# 3_Sensors.net
KiCad netlist of a schematic drawn in Altium Designer
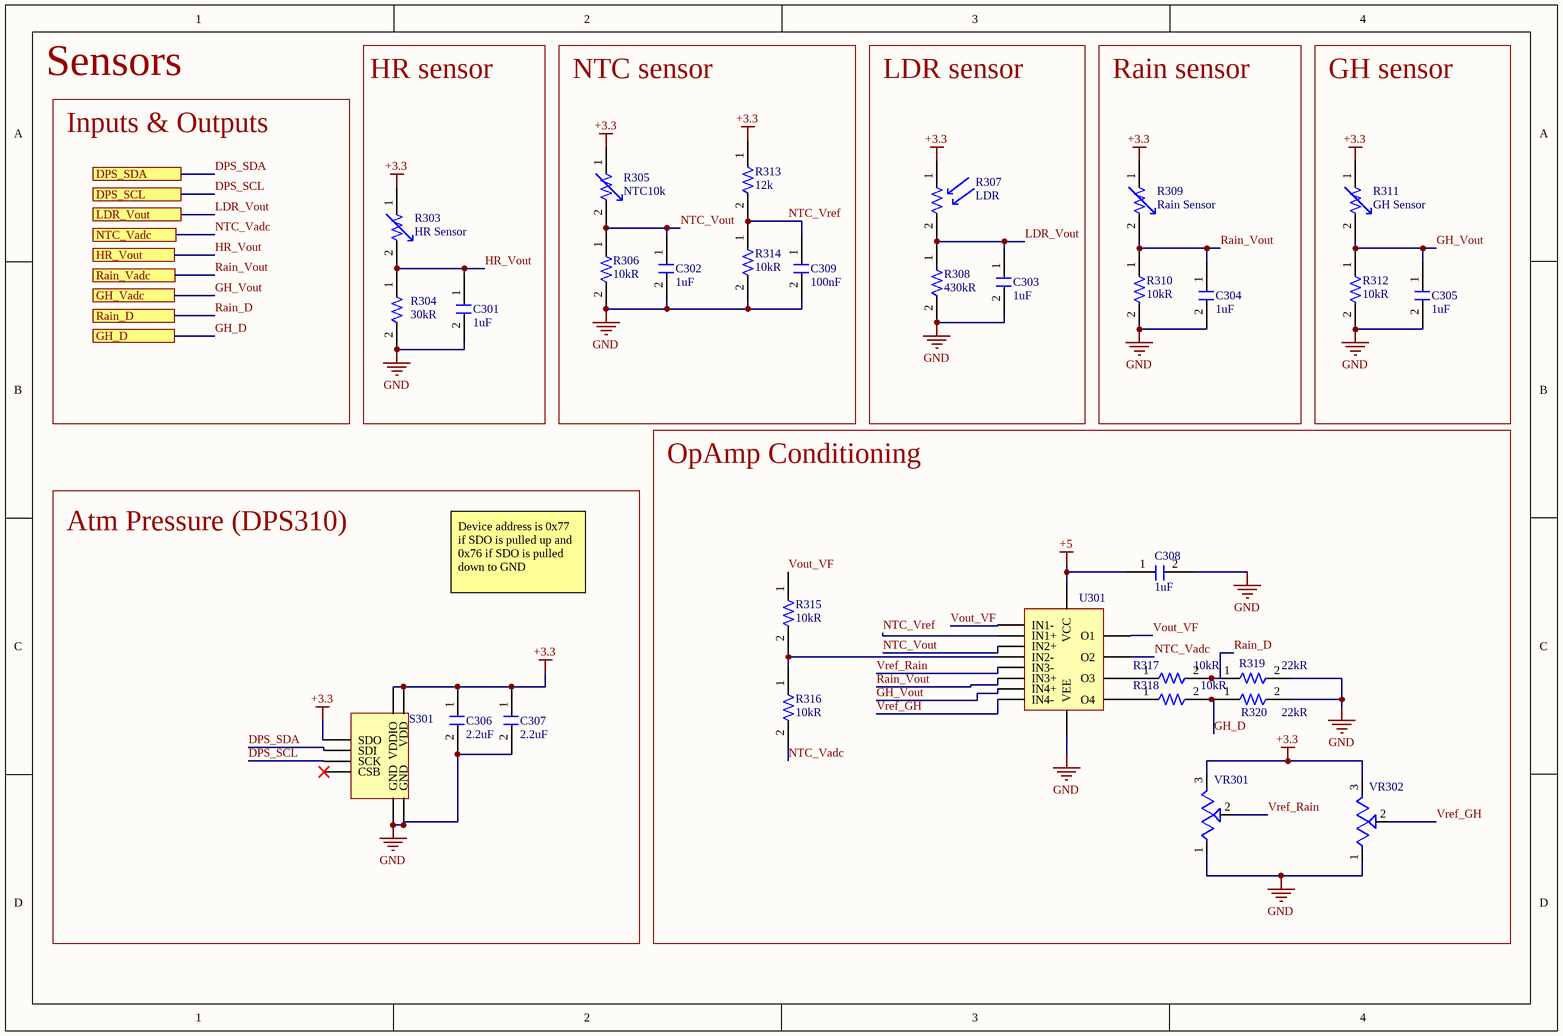
[diagram p0: [3]Sensors.SchDoc]

(export (version "E")
  (design (tool "Eeschema 10.0.6"))
  (components
    (comp (ref "C301")
      (value "885012208036")
      (footprint "C1206FNPC-RW")
      (description "Cap Cer 1UF 16V X7R 1206")
      (fields
        (field (name "MANUFACTURER") "Wurth Electronics")
        (field (name "TOLERANCE") "10%")
        (field (name "CAPACITANCE") "1uF")
        (field (name ".CREATOR") "GP")
      )
      (libsource (lib "Passives") (part "C1u-16V-1206FNPC-X7R"))
    )
    (comp (ref "C302")
      (value "885012208036")
      (footprint "C1206FNPC-RW")
      (description "Cap Cer 1UF 16V X7R 1206")
      (fields
        (field (name "MANUFACTURER") "Wurth Electronics")
        (field (name "TOLERANCE") "10%")
        (field (name "CAPACITANCE") "1uF")
        (field (name ".CREATOR") "GP")
      )
      (libsource (lib "Passives") (part "C1u-16V-1206FNPC-X7R"))
    )
    (comp (ref "C303")
      (value "885012208036")
      (footprint "C1206FNPC-RW")
      (description "Cap Cer 1UF 16V X7R 1206")
      (fields
        (field (name "MANUFACTURER") "Wurth Electronics")
        (field (name "TOLERANCE") "10%")
        (field (name "CAPACITANCE") "1uF")
        (field (name ".CREATOR") "GP")
      )
      (libsource (lib "Passives") (part "C1u-16V-1206FNPC-X7R"))
    )
    (comp (ref "C304")
      (value "885012208036")
      (footprint "C1206FNPC-RW")
      (description "Cap Cer 1UF 16V X7R 1206")
      (fields
        (field (name "MANUFACTURER") "Wurth Electronics")
        (field (name "TOLERANCE") "10%")
        (field (name "CAPACITANCE") "1uF")
        (field (name ".CREATOR") "GP")
      )
      (libsource (lib "Passives") (part "C1u-16V-1206FNPC-X7R"))
    )
    (comp (ref "C305")
      (value "885012208036")
      (footprint "C1206FNPC-RW")
      (description "Cap Cer 1UF 16V X7R 1206")
      (fields
        (field (name "MANUFACTURER") "Wurth Electronics")
        (field (name "TOLERANCE") "10%")
        (field (name "CAPACITANCE") "1uF")
        (field (name ".CREATOR") "GP")
      )
      (libsource (lib "Passives") (part "C1u-16V-1206FNPC-X7R"))
    )
    (comp (ref "C306")
      (value "2.2uF")
      (footprint "C0805FNPC-W")
      (libsource (lib "Passives") (part "C2.2u-16V-0805FTK"))
    )
    (comp (ref "C307")
      (value "2.2uF")
      (footprint "C0805FNPC-W")
      (libsource (lib "Passives") (part "C2.2u-16V-0805FTK"))
    )
    (comp (ref "C308")
      (value "885012208036")
      (footprint "C1206FNPC-RW")
      (description "Cap Cer 1UF 16V X7R 1206")
      (fields
        (field (name "MANUFACTURER") "Wurth Electronics")
        (field (name "TOLERANCE") "10%")
        (field (name "CAPACITANCE") "1uF")
        (field (name ".CREATOR") "GP")
      )
      (libsource (lib "Passives") (part "C1u-16V-1206FNPC-X7R"))
    )
    (comp (ref "C309")
      (value "885012208009")
      (footprint "C1206FNPC-RW")
      (description "Cap, 0.1ΜF, 10V, 10%, X7R, 1206")
      (fields
        (field (name "TOLERANCE") "10%")
        (field (name "CAPACITANCE") "100nF")
        (field (name ".CREATOR") "GP")
      )
      (libsource (lib "Passives") (part "C100n-10V-1206FNPC-X7R"))
    )
    (comp (ref "R303")
      (value "HR Sensor")
      (footprint "HR_Sensor")
      (description "Resistive HR Sensor. R30k at 60%@25ºC")
      (libsource (lib "CommonFiles_Library") (part "Resistive_HR_Sensor"))
    )
    (comp (ref "R304")
      (value "CRCW120630K0FKEA")
      (footprint "R1206FTK-W")
      (description "Res Thick Film 1206 30K Ohm 1% 1/4W ±100ppm/°C Molded SMD SMD Paper T/R")
      (fields
        (field (name "MANUFACTURER") "Vishay")
        (field (name "TOLERANCE") "1%")
        (field (name "RESISTANCE") "30kR")
        (field (name ".CREATOR") "GP")
      )
      (libsource (lib "Passives") (part "R30k-1206FTK"))
    )
    (comp (ref "R305")
      (value "NTC10k")
      (footprint "NTC10k_0805")
      (libsource (lib "CommonFiles_Library") (part "NTC_10k_0805"))
    )
    (comp (ref "R306")
      (value "CR0805-JW-103ELF")
      (footprint "R0805FTK")
      (fields
        (field (name "TOLERANCE") "5%")
        (field (name "RESISTANCE") "10kR")
        (field (name ".CREATOR") "DR")
      )
      (libsource (lib "Passives") (part "R10k-0805FTK"))
    )
    (comp (ref "R307")
      (value "LDR")
      (footprint "HR_Sensor")
      (libsource (lib "CommonFiles_Library") (part "LDR_LightSensor"))
    )
    (comp (ref "R308")
      (value "430kR")
      (footprint "R0805FTK")
      (libsource (lib "Passives") (part "R430k-0805FTK"))
    )
    (comp (ref "R309")
      (value "Rain Sensor")
      (footprint "EXTERNAL_SENSOR")
      (libsource (lib "CommonFiles_Library") (part "RainSensor_Resisitve"))
    )
    (comp (ref "R310")
      (value "CR0805-JW-103ELF")
      (footprint "R0805FTK")
      (fields
        (field (name "TOLERANCE") "5%")
        (field (name "RESISTANCE") "10kR")
        (field (name ".CREATOR") "DR")
      )
      (libsource (lib "Passives") (part "R10k-0805FTK"))
    )
    (comp (ref "R311")
      (value "GH Sensor")
      (footprint "EXTERNAL_SENSOR")
      (libsource (lib "CommonFiles_Library") (part "GH_Resistive_Sensor"))
    )
    (comp (ref "R312")
      (value "CR0805-JW-103ELF")
      (footprint "R0805FTK")
      (fields
        (field (name "TOLERANCE") "5%")
        (field (name "RESISTANCE") "10kR")
        (field (name ".CREATOR") "DR")
      )
      (libsource (lib "Passives") (part "R10k-0805FTK"))
    )
    (comp (ref "R313")
      (value "12k")
      (footprint "R1206")
      (libsource (lib "CommonFiles_Library") (part "R12k-1206"))
    )
    (comp (ref "R314")
      (value "CR0805-JW-103ELF")
      (footprint "R0805FTK")
      (fields
        (field (name "TOLERANCE") "5%")
        (field (name "RESISTANCE") "10kR")
        (field (name ".CREATOR") "DR")
      )
      (libsource (lib "Passives") (part "R10k-0805FTK"))
    )
    (comp (ref "R315")
      (value "CR0805-JW-103ELF")
      (footprint "R0805FTK")
      (fields
        (field (name "TOLERANCE") "5%")
        (field (name "RESISTANCE") "10kR")
        (field (name ".CREATOR") "DR")
      )
      (libsource (lib "Passives") (part "R10k-0805FTK"))
    )
    (comp (ref "R316")
      (value "CR0805-JW-103ELF")
      (footprint "R0805FTK")
      (fields
        (field (name "TOLERANCE") "5%")
        (field (name "RESISTANCE") "10kR")
        (field (name ".CREATOR") "DR")
      )
      (libsource (lib "Passives") (part "R10k-0805FTK"))
    )
    (comp (ref "R317")
      (value "CR0805-JW-103ELF")
      (footprint "R0805FTK")
      (fields
        (field (name "TOLERANCE") "5%")
        (field (name "RESISTANCE") "10kR")
        (field (name ".CREATOR") "DR")
      )
      (libsource (lib "Passives") (part "R10k-0805FTK"))
    )
    (comp (ref "R318")
      (value "CR0805-JW-103ELF")
      (footprint "R0805FTK")
      (fields
        (field (name "TOLERANCE") "5%")
        (field (name "RESISTANCE") "10kR")
        (field (name ".CREATOR") "DR")
      )
      (libsource (lib "Passives") (part "R10k-0805FTK"))
    )
    (comp (ref "R319")
      (value "22kR")
      (footprint "R0805FTK")
      (libsource (lib "Passives") (part "R22k-0805FTK"))
    )
    (comp (ref "R320")
      (value "22kR")
      (footprint "R0805FTK")
      (libsource (lib "Passives") (part "R22k-0805FTK"))
    )
    (comp (ref "S301")
      (value "DPS310XTSA1")
      (footprint "XDCR_DPS310XTSA1")
      (description "DPS310 Digital Pressure Sensor")
      (libsource (lib "CommonFiles_Library") (part "AtmPressureSensor_DPS310XTSA1"))
    )
    (comp (ref "U301")
      (value "OpAmp")
      (footprint "LM324_OpAmp")
      (libsource (lib "CommonFiles_Library") (part "LM324_OpAmp"))
    )
    (comp (ref "VR301")
      (value "Trimmer_10k_THT")
      (footprint "TRIM_3362P-1-103LF")
      (description "Trimmer, Cermet, Rest 10 Kilohms, PCB, 1 Turns, Pwr-Rtg 0.5 W, Tol 10% ¦ Bourns 3362P-1-103LF")
      (fields (field (name "MF") "Bourns") (field (name "MP") "3362P-1-103LF"))
      (libsource (lib "CommonFiles_Library") (part "Trimmer_10k_THT"))
    )
    (comp (ref "VR302")
      (value "Trimmer_10k_THT")
      (footprint "TRIM_3362P-1-103LF")
      (description "Trimmer, Cermet, Rest 10 Kilohms, PCB, 1 Turns, Pwr-Rtg 0.5 W, Tol 10% ¦ Bourns 3362P-1-103LF")
      (fields (field (name "MF") "Bourns") (field (name "MP") "3362P-1-103LF"))
      (libsource (lib "CommonFiles_Library") (part "Trimmer_10k_THT"))
    )
  )
  (nets
    (net (code "1") (name "+3.3") (class "Default")
      (node (ref "C306") (pin "1") (pinfunction "1_1") (pintype "passive"))
      (node (ref "C307") (pin "1") (pinfunction "1_1") (pintype "passive"))
      (node (ref "R303") (pin "1") (pinfunction "2_1") (pintype "passive"))
      (node (ref "R305") (pin "1") (pinfunction "2_1") (pintype "passive"))
      (node (ref "R307") (pin "1") (pinfunction "2_1") (pintype "passive"))
      (node (ref "R309") (pin "1") (pinfunction "2_1") (pintype "passive"))
      (node (ref "R311") (pin "1") (pinfunction "2_1") (pintype "passive"))
      (node (ref "R313") (pin "1") (pinfunction "2_1") (pintype "passive"))
      (node (ref "S301") (pin "5") (pinfunction "SDO_5") (pintype "passive"))
      (node (ref "S301") (pin "6") (pinfunction "VDDIO_6") (pintype "passive"))
      (node (ref "S301") (pin "8") (pinfunction "VDD_8") (pintype "passive"))
      (node (ref "VR301") (pin "3") (pinfunction "CW_3") (pintype "passive"))
      (node (ref "VR302") (pin "3") (pinfunction "CW_3") (pintype "passive"))
    )
    (net (code "2") (name "+5") (class "Default")
      (node (ref "C308") (pin "1") (pinfunction "1_1") (pintype "passive"))
      (node (ref "U301") (pin "4") (pinfunction "VCC_4") (pintype "passive"))
    )
    (net (code "3") (name "/DPS_SCL") (class "Default")
      (node (ref "S301") (pin "4") (pinfunction "SCK_4") (pintype "passive"))
    )
    (net (code "4") (name "/DPS_SDA") (class "Default")
      (node (ref "S301") (pin "3") (pinfunction "SDI_3") (pintype "passive"))
    )
    (net (code "5") (name "/GH_D") (class "Default")
      (node (ref "R318") (pin "2") (pinfunction "2_2") (pintype "passive"))
      (node (ref "R320") (pin "1") (pinfunction "1_1") (pintype "passive"))
    )
    (net (code "6") (name "/GH_Vout") (class "Default")
      (node (ref "C305") (pin "1") (pinfunction "1_1") (pintype "passive"))
      (node (ref "R311") (pin "2") (pinfunction "2_2") (pintype "passive"))
      (node (ref "R312") (pin "1") (pinfunction "1_1") (pintype "passive"))
      (node (ref "U301") (pin "12") (pinfunction "IN4+_12") (pintype "passive"))
    )
    (net (code "7") (name "/HR_Vout") (class "Default")
      (node (ref "C301") (pin "1") (pinfunction "1_1") (pintype "passive"))
      (node (ref "R303") (pin "2") (pinfunction "2_2") (pintype "passive"))
      (node (ref "R304") (pin "1") (pinfunction "1_1") (pintype "passive"))
    )
    (net (code "8") (name "/LDR_Vout") (class "Default")
      (node (ref "C303") (pin "1") (pinfunction "1_1") (pintype "passive"))
      (node (ref "R307") (pin "2") (pinfunction "2_2") (pintype "passive"))
      (node (ref "R308") (pin "1") (pinfunction "1_1") (pintype "passive"))
    )
    (net (code "9") (name "/NTC_Vadc") (class "Default")
      (node (ref "R316") (pin "2") (pinfunction "2_2") (pintype "passive"))
      (node (ref "U301") (pin "7") (pinfunction "O2_7") (pintype "passive"))
    )
    (net (code "10") (name "/NTC_Vout") (class "Default")
      (node (ref "C302") (pin "1") (pinfunction "1_1") (pintype "passive"))
      (node (ref "R305") (pin "2") (pinfunction "2_2") (pintype "passive"))
      (node (ref "R306") (pin "1") (pinfunction "1_1") (pintype "passive"))
      (node (ref "U301") (pin "5") (pinfunction "IN2+_5") (pintype "passive"))
    )
    (net (code "11") (name "/NTC_Vref") (class "Default")
      (node (ref "C309") (pin "1") (pinfunction "1_1") (pintype "passive"))
      (node (ref "R313") (pin "2") (pinfunction "2_2") (pintype "passive"))
      (node (ref "R314") (pin "1") (pinfunction "1_1") (pintype "passive"))
      (node (ref "U301") (pin "3") (pinfunction "IN1+_3") (pintype "passive"))
    )
    (net (code "12") (name "/Rain_D") (class "Default")
      (node (ref "R317") (pin "2") (pinfunction "2_2") (pintype "passive"))
      (node (ref "R319") (pin "1") (pinfunction "1_1") (pintype "passive"))
    )
    (net (code "13") (name "/Rain_Vout") (class "Default")
      (node (ref "C304") (pin "1") (pinfunction "1_1") (pintype "passive"))
      (node (ref "R309") (pin "2") (pinfunction "2_2") (pintype "passive"))
      (node (ref "R310") (pin "1") (pinfunction "1_1") (pintype "passive"))
      (node (ref "U301") (pin "10") (pinfunction "IN3+_10") (pintype "passive"))
    )
    (net (code "14") (name "/Vout_VF") (class "Default")
      (node (ref "R315") (pin "1") (pinfunction "1_1") (pintype "passive"))
      (node (ref "U301") (pin "1") (pinfunction "O1_1") (pintype "passive"))
      (node (ref "U301") (pin "2") (pinfunction "IN1-_2") (pintype "passive"))
    )
    (net (code "15") (name "/Vref_GH") (class "Default")
      (node (ref "U301") (pin "13") (pinfunction "IN4-_13") (pintype "passive"))
      (node (ref "VR302") (pin "2") (pinfunction "WIPER_2") (pintype "passive"))
    )
    (net (code "16") (name "/Vref_Rain") (class "Default")
      (node (ref "U301") (pin "9") (pinfunction "IN3-_9") (pintype "passive"))
      (node (ref "VR301") (pin "2") (pinfunction "WIPER_2") (pintype "passive"))
    )
    (net (code "17") (name "GND") (class "Default")
      (node (ref "C301") (pin "2") (pinfunction "2_2") (pintype "passive"))
      (node (ref "C302") (pin "2") (pinfunction "2_2") (pintype "passive"))
      (node (ref "C303") (pin "2") (pinfunction "2_2") (pintype "passive"))
      (node (ref "C304") (pin "2") (pinfunction "2_2") (pintype "passive"))
      (node (ref "C305") (pin "2") (pinfunction "2_2") (pintype "passive"))
      (node (ref "C306") (pin "2") (pinfunction "2_2") (pintype "passive"))
      (node (ref "C307") (pin "2") (pinfunction "2_2") (pintype "passive"))
      (node (ref "C308") (pin "2") (pinfunction "2_2") (pintype "passive"))
      (node (ref "C309") (pin "2") (pinfunction "2_2") (pintype "passive"))
      (node (ref "R304") (pin "2") (pinfunction "2_2") (pintype "passive"))
      (node (ref "R306") (pin "2") (pinfunction "2_2") (pintype "passive"))
      (node (ref "R308") (pin "2") (pinfunction "2_2") (pintype "passive"))
      (node (ref "R310") (pin "2") (pinfunction "2_2") (pintype "passive"))
      (node (ref "R312") (pin "2") (pinfunction "2_2") (pintype "passive"))
      (node (ref "R314") (pin "2") (pinfunction "2_2") (pintype "passive"))
      (node (ref "R319") (pin "2") (pinfunction "2_2") (pintype "passive"))
      (node (ref "R320") (pin "2") (pinfunction "2_2") (pintype "passive"))
      (node (ref "S301") (pin "1") (pinfunction "GND_1") (pintype "passive"))
      (node (ref "S301") (pin "7") (pinfunction "GND_7") (pintype "passive"))
      (node (ref "U301") (pin "11") (pinfunction "VEE_11") (pintype "passive"))
      (node (ref "VR301") (pin "1") (pinfunction "CCW_1") (pintype "passive"))
      (node (ref "VR302") (pin "1") (pinfunction "CCW_1") (pintype "passive"))
    )
    (net (code "18") (name "Net-(U301-IN2-)") (class "Default")
      (node (ref "R315") (pin "2") (pinfunction "2_2") (pintype "passive"))
      (node (ref "R316") (pin "1") (pinfunction "1_1") (pintype "passive"))
      (node (ref "U301") (pin "6") (pinfunction "IN2-_6") (pintype "passive"))
    )
    (net (code "19") (name "Net-(U301-O3)") (class "Default")
      (node (ref "R317") (pin "1") (pinfunction "1_1") (pintype "passive"))
      (node (ref "U301") (pin "8") (pinfunction "O3_8") (pintype "passive"))
    )
    (net (code "20") (name "Net-(U301-O4)") (class "Default")
      (node (ref "R318") (pin "1") (pinfunction "1_1") (pintype "passive"))
      (node (ref "U301") (pin "14") (pinfunction "O4_14") (pintype "passive"))
    )
    (net (code "21") (name "unconnected-(S301-CSB-Pad2)") (class "Default")
      (node (ref "S301") (pin "2") (pinfunction "CSB_2") (pintype "passive+no_connect"))
    )
  )
)
